# IR2101_irfz44.net
KiCad netlist of a schematic drawn in Altium Designer
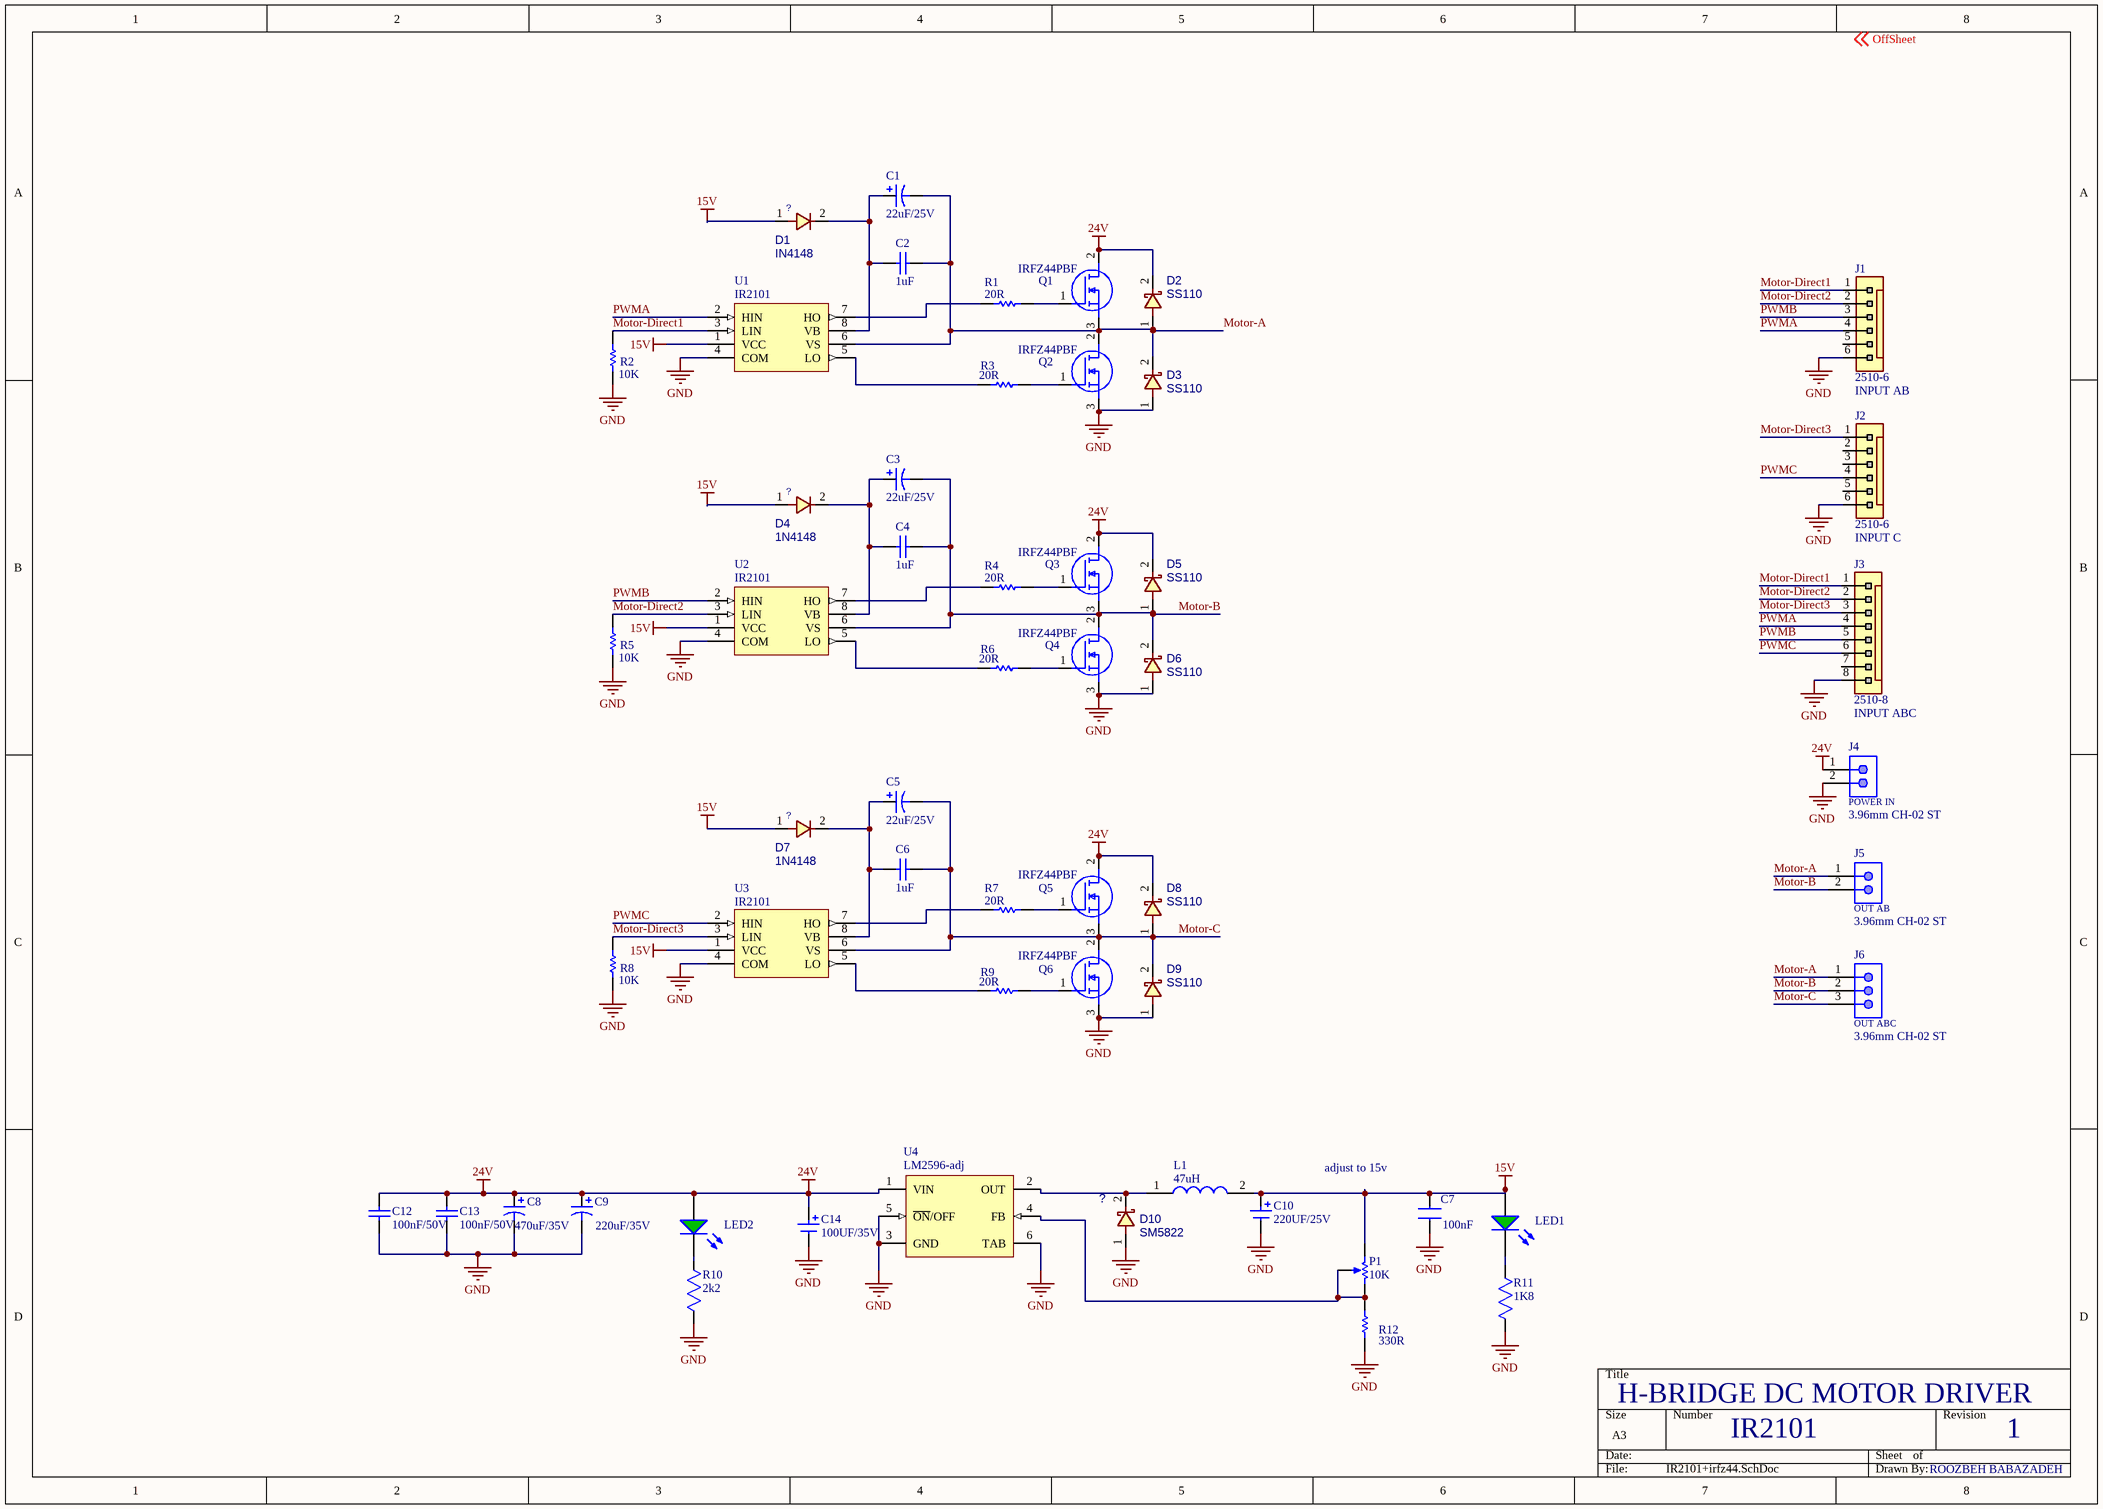
[diagram p0: IR2101+irfz44.SchDoc]

(export (version "E")
  (design (tool "Eeschema 10.0.6"))
  (components
    (comp (ref "C1")
      (value "22uF/25V")
      (footprint "C_EL_6X11")
      (description "Polarized Capacitor (Radial)")
      (fields (field (name "PUBLISHER") "Altium Limited"))
      (libsource (lib "Miscellaneous Devices") (part "Cap Pol1"))
    )
    (comp (ref "C2")
      (value "1uF")
      (footprint "C0805E")
      (description "Capacitor")
      (fields (field (name "PUBLISHER") "Altium Limited"))
      (libsource (lib "Miscellaneous Devices") (part "Cap"))
    )
    (comp (ref "C3")
      (value "22uF/25V")
      (footprint "C_EL_6X11")
      (description "Polarized Capacitor (Radial)")
      (fields (field (name "PUBLISHER") "Altium Limited"))
      (libsource (lib "Miscellaneous Devices") (part "Cap Pol1"))
    )
    (comp (ref "C4")
      (value "1uF")
      (footprint "C0805E")
      (description "Capacitor")
      (fields (field (name "PUBLISHER") "Altium Limited"))
      (libsource (lib "Miscellaneous Devices") (part "Cap"))
    )
    (comp (ref "C5")
      (value "22uF/25V")
      (footprint "C_EL_6X11")
      (description "Polarized Capacitor (Radial)")
      (fields (field (name "PUBLISHER") "Altium Limited"))
      (libsource (lib "Miscellaneous Devices") (part "Cap Pol1"))
    )
    (comp (ref "C6")
      (value "1uF")
      (footprint "C0805E")
      (description "Capacitor")
      (fields (field (name "PUBLISHER") "Altium Limited"))
      (libsource (lib "Miscellaneous Devices") (part "Cap"))
    )
    (comp (ref "C7") (value "100nF") (footprint "C0805E") (libsource (lib "OTHER") (part "C")))
    (comp (ref "C8")
      (value "470uF/35V")
      (footprint "C_EL_10X12")
      (description "63VDC")
      (libsource (lib "My_LIB") (part "Cap 220uF"))
    )
    (comp (ref "C9")
      (value "220uF/35V")
      (footprint "C_EL_10X12")
      (description "63VDC")
      (libsource (lib "My_LIB") (part "Cap 220uF"))
    )
    (comp (ref "C10")
      (value "220UF/25V")
      (footprint "C_EL_10X12")
      (libsource (lib "OTHER") (part "CAP_ELECTRO_POLIMER"))
    )
    (comp (ref "C12")
      (value "100nF/50V")
      (footprint "C_PLY_7X6")
      (libsource (lib "My_LIB") (part "Cap 100nF"))
    )
    (comp (ref "C13")
      (value "100nF/50V")
      (footprint "C_PLY_7X6")
      (description "63VDC")
      (fields (field (name "PUBLISHER") "Altium Limited"))
      (libsource (lib "Miscellaneous Devices") (part "Cap"))
    )
    (comp (ref "C14")
      (value "100UF/35V")
      (footprint "C_EL_10X12")
      (libsource (lib "OTHER") (part "CAP_ELECTRO_POLIMER"))
    )
    (comp (ref "D1")
      (value "IN4148")
      (footprint "D_SOD123W")
      (description "DIODE, GENERAL PURPOSE, 50V/1A")
      (fields
        (field (name "MANF") "MANF")
        (field (name "MANF_P#") "1N4001")
        (field (name "ALTIUM_VALUE") "?")
      )
      (libsource (lib "diode") (part "DIODE"))
    )
    (comp (ref "D2")
      (value "SS110")
      (footprint "D_SMA")
      (description "DIODE, SCHOTTKY, 40V, 1A")
      (fields (field (name "MANF") "DIODES") (field (name "MANF_P#") "1N5819HW-7-F"))
      (libsource (lib "diode") (part "SCHOTTKY"))
    )
    (comp (ref "D3")
      (value "SS110")
      (footprint "D_SMA")
      (description "DIODE, SCHOTTKY, 40V, 1A")
      (fields (field (name "MANF") "DIODES") (field (name "MANF_P#") "1N5819HW-7-F"))
      (libsource (lib "diode") (part "SCHOTTKY"))
    )
    (comp (ref "D4")
      (value "1N4148")
      (footprint "D_SOD123W")
      (description "DIODE, GENERAL PURPOSE, 50V/1A")
      (fields
        (field (name "MANF") "MANF")
        (field (name "MANF_P#") "1N4001")
        (field (name "ALTIUM_VALUE") "?")
      )
      (libsource (lib "diode") (part "DIODE"))
    )
    (comp (ref "D5")
      (value "SS110")
      (footprint "D_SMA")
      (description "DIODE, SCHOTTKY, 40V, 1A")
      (fields (field (name "MANF") "DIODES") (field (name "MANF_P#") "1N5819HW-7-F"))
      (libsource (lib "diode") (part "SCHOTTKY"))
    )
    (comp (ref "D6")
      (value "SS110")
      (footprint "D_SMA")
      (description "DIODE, SCHOTTKY, 40V, 1A")
      (fields (field (name "MANF") "DIODES") (field (name "MANF_P#") "1N5819HW-7-F"))
      (libsource (lib "diode") (part "SCHOTTKY"))
    )
    (comp (ref "D7")
      (value "1N4148")
      (footprint "D_SOD123W")
      (description "DIODE, GENERAL PURPOSE, 50V/1A")
      (fields
        (field (name "MANF") "MANF")
        (field (name "MANF_P#") "1N4001")
        (field (name "ALTIUM_VALUE") "?")
      )
      (libsource (lib "diode") (part "DIODE"))
    )
    (comp (ref "D8")
      (value "SS110")
      (footprint "D_SMA")
      (description "DIODE, SCHOTTKY, 40V, 1A")
      (fields (field (name "MANF") "DIODES") (field (name "MANF_P#") "1N5819HW-7-F"))
      (libsource (lib "diode") (part "SCHOTTKY"))
    )
    (comp (ref "D9")
      (value "SS110")
      (footprint "D_SMA")
      (description "DIODE, SCHOTTKY, 40V, 1A")
      (fields (field (name "MANF") "DIODES") (field (name "MANF_P#") "1N5819HW-7-F"))
      (libsource (lib "diode") (part "SCHOTTKY"))
    )
    (comp (ref "D10")
      (value "SM5822")
      (footprint "D_SMB")
      (description "DIODE, SCHOTTKY, 40V, 1A")
      (fields
        (field (name "MANF") "DIODES")
        (field (name "MANF_P#") "1N5819HW-7-F")
        (field (name "ALTIUM_VALUE") "?")
      )
      (libsource (lib "diode") (part "SCHOTTKY"))
    )
    (comp (ref "J1")
      (value "2510-6")
      (footprint "WF_6")
      (description "Header, WF, Pitch: 2.54mm")
      (fields (field (name "ALTIUM_VALUE") "INPUT AB"))
      (libsource (lib "xh-xhr-wf-hhdr-hh6r") (part "HDRWF_6"))
    )
    (comp (ref "J2")
      (value "2510-6")
      (footprint "WF_6")
      (description "Header, WF, Pitch: 2.54mm")
      (fields (field (name "ALTIUM_VALUE") "INPUT C"))
      (libsource (lib "xh-xhr-wf-hhdr-hh6r") (part "HDRWF_6"))
    )
    (comp (ref "J3")
      (value "2510-8")
      (footprint "WF_8")
      (description "Header, WF, Pitch: 2.54mm")
      (fields (field (name "ALTIUM_VALUE") "INPUT ABC"))
      (libsource (lib "xh-xhr-wf-hhdr-hh6r") (part "HDRWF_8"))
    )
    (comp (ref "J4")
      (value "POWER IN")
      (footprint "PWL_2")
      (description "CH-02 ST pitch 3.96mm, Single Row, Vertical, 2pin")
      (fields
        (field (name "PART NUMBER") "61300211121")
        (field (name "PACKAGING") "3.96mm CH-02 ST")
        (field (name "PUBLISHER") "Wurth Elektronik")
      )
      (libsource (lib "sip m") (part "sip 2"))
    )
    (comp (ref "J5")
      (value "OUT AB")
      (footprint "PWL_2")
      (description "CH-02 ST pitch 3.96mm, Single Row, Vertical, 2pin")
      (fields
        (field (name "PART NUMBER") "61300211121")
        (field (name "PACKAGING") "3.96mm CH-02 ST")
        (field (name "PUBLISHER") "Wurth Elektronik")
      )
      (libsource (lib "sip m") (part "sip 2"))
    )
    (comp (ref "J6")
      (value "OUT ABC")
      (footprint "PWL_3")
      (description "CH-02 STpitch 3.96mm, Single Row, Vertical, 3pin")
      (fields
        (field (name "PART NUMBER") "61300311121")
        (field (name "PACKAGING") "3.96mm CH-02 ST")
        (field (name "PUBLISHER") "Wurth Elektronik")
      )
      (libsource (lib "sip m") (part "sip 3"))
    )
    (comp (ref "L1")
      (value "47uH")
      (footprint "CDRH127LDNP560MC-12*12")
      (description "Inductor")
      (fields
        (field (name "MANUFACTURER_PART_NUMBER") "CDRH127/LDNP-560MC")
        (field (name "MOUSER PART NUMBER") "851-CDRH127LDNP560MC")
      )
      (libsource (lib "*") (part "CDRH127_LDNP-560MC"))
    )
    (comp (ref "LED1") (value "LED3mm") (footprint "LED1206RED") (libsource (lib "OTHER") (part "LED3mm")))
    (comp (ref "LED2") (value "LED3mm") (footprint "LED1206RED") (libsource (lib "OTHER") (part "LED3mm")))
    (comp (ref "P1")
      (value "10K")
      (footprint "POT_3296W")
      (description "Potentiometer")
      (libsource (lib "My_LIB") (part "Multi-Turn"))
    )
    (comp (ref "Q1")
      (value "IRFZ44PBF")
      (footprint "TO-254")
      (description "MOSFET (N-Channel)")
      (fields (field (name "MOUSER PART NUMBER") "844-IRFZ44PBF"))
      (libsource (lib "*") (part "IRFZ44PBF"))
    )
    (comp (ref "Q2")
      (value "IRFZ44PBF")
      (footprint "TO-254")
      (description "MOSFET (N-Channel)")
      (fields (field (name "MOUSER PART NUMBER") "844-IRFZ44PBF"))
      (libsource (lib "*") (part "IRFZ44PBF"))
    )
    (comp (ref "Q3")
      (value "IRFZ44PBF")
      (footprint "TO-254")
      (description "MOSFET (N-Channel)")
      (fields (field (name "MOUSER PART NUMBER") "844-IRFZ44PBF"))
      (libsource (lib "*") (part "IRFZ44PBF"))
    )
    (comp (ref "Q4")
      (value "IRFZ44PBF")
      (footprint "TO-254")
      (description "MOSFET (N-Channel)")
      (fields (field (name "MOUSER PART NUMBER") "844-IRFZ44PBF"))
      (libsource (lib "*") (part "IRFZ44PBF"))
    )
    (comp (ref "Q5")
      (value "IRFZ44PBF")
      (footprint "TO-254")
      (description "MOSFET (N-Channel)")
      (fields (field (name "MOUSER PART NUMBER") "844-IRFZ44PBF"))
      (libsource (lib "*") (part "IRFZ44PBF"))
    )
    (comp (ref "Q6")
      (value "IRFZ44PBF")
      (footprint "TO-254")
      (description "MOSFET (N-Channel)")
      (fields (field (name "MOUSER PART NUMBER") "844-IRFZ44PBF"))
      (libsource (lib "*") (part "IRFZ44PBF"))
    )
    (comp (ref "R1")
      (value "20R")
      (footprint "R0805")
      (description "Resistor")
      (fields (field (name "PUBLISHER") "Altium Limited"))
      (libsource (lib "Miscellaneous Devices") (part "Res1"))
    )
    (comp (ref "R2")
      (value "10K")
      (footprint "R0805")
      (description "Resistor")
      (fields (field (name "PUBLISHER") "Altium Limited"))
      (libsource (lib "Miscellaneous Devices") (part "Res1"))
    )
    (comp (ref "R3")
      (value "20R")
      (footprint "R0805")
      (description "Resistor")
      (fields (field (name "PUBLISHER") "Altium Limited"))
      (libsource (lib "Miscellaneous Devices") (part "Res1"))
    )
    (comp (ref "R4")
      (value "20R")
      (footprint "R0805")
      (description "Resistor")
      (fields (field (name "PUBLISHER") "Altium Limited"))
      (libsource (lib "Miscellaneous Devices") (part "Res1"))
    )
    (comp (ref "R5")
      (value "10K")
      (footprint "R0805")
      (description "Resistor")
      (fields (field (name "PUBLISHER") "Altium Limited"))
      (libsource (lib "Miscellaneous Devices") (part "Res1"))
    )
    (comp (ref "R6")
      (value "20R")
      (footprint "R0805")
      (description "Resistor")
      (fields (field (name "PUBLISHER") "Altium Limited"))
      (libsource (lib "Miscellaneous Devices") (part "Res1"))
    )
    (comp (ref "R7")
      (value "20R")
      (footprint "R0805")
      (description "Resistor")
      (fields (field (name "Comment") "Res1") (field (name "PUBLISHER") "Altium Limited"))
      (libsource (lib "Miscellaneous Devices") (part "Res1"))
    )
    (comp (ref "R8")
      (value "10K")
      (footprint "R0805")
      (description "Resistor")
      (fields (field (name "PUBLISHER") "Altium Limited"))
      (libsource (lib "Miscellaneous Devices") (part "Res1"))
    )
    (comp (ref "R9")
      (value "20R")
      (footprint "R0805")
      (description "Resistor")
      (fields (field (name "Comment") "Res1") (field (name "PUBLISHER") "Altium Limited"))
      (libsource (lib "Miscellaneous Devices") (part "Res1"))
    )
    (comp (ref "R10") (value "2k2") (footprint "R0805") (libsource (lib "OTHER") (part "R")))
    (comp (ref "R11") (value "1K8") (footprint "R0805") (libsource (lib "OTHER") (part "R")))
    (comp (ref "R12")
      (value "330R")
      (footprint "R0805")
      (description "Resistor")
      (fields (field (name "PUBLISHER") "Altium Limited"))
      (libsource (lib "Miscellaneous Devices") (part "Res1"))
    )
    (comp (ref "U1")
      (value "IR2101")
      (footprint "SO_8")
      (description "High and Low Side Driver")
      (fields (field (name "PUBLISHER") "Altium Limited"))
      (libsource (lib "IR Interface Bridge Driver") (part "IR2101"))
    )
    (comp (ref "U2")
      (value "IR2101")
      (footprint "SO_8")
      (description "High and Low Side Driver")
      (fields (field (name "PUBLISHER") "Altium Limited"))
      (libsource (lib "IR Interface Bridge Driver") (part "IR2101"))
    )
    (comp (ref "U3")
      (value "IR2101")
      (footprint "SO_8")
      (description "High and Low Side Driver")
      (fields (field (name "PUBLISHER") "Altium Limited"))
      (libsource (lib "IR Interface Bridge Driver") (part "IR2101"))
    )
    (comp (ref "U4")
      (value "LM2596-adj")
      (footprint "to-263-5 5d2pak LM2596S")
      (libsource (lib "POWER") (part "LM2596s"))
    )
  )
  (nets
    (net (code "1") (name "/Motor-A") (class "Default")
      (node (ref "C1") (pin "2") (pinfunction "2_2") (pintype "passive"))
      (node (ref "C2") (pin "2") (pinfunction "2_2") (pintype "passive"))
      (node (ref "D2") (pin "1") (pinfunction "1_1") (pintype "passive"))
      (node (ref "D3") (pin "2") (pinfunction "2_2") (pintype "passive"))
      (node (ref "J5") (pin "1") (pinfunction "1_1") (pintype "passive"))
      (node (ref "J6") (pin "1") (pinfunction "1_1") (pintype "passive"))
      (node (ref "Q1") (pin "3") (pinfunction "S_3") (pintype "passive"))
      (node (ref "Q2") (pin "2") (pinfunction "D_2") (pintype "passive"))
      (node (ref "U1") (pin "6") (pinfunction "VS_6") (pintype "power_in"))
    )
    (net (code "2") (name "/Motor-B") (class "Default")
      (node (ref "C3") (pin "2") (pinfunction "2_2") (pintype "passive"))
      (node (ref "C4") (pin "2") (pinfunction "2_2") (pintype "passive"))
      (node (ref "D5") (pin "1") (pinfunction "1_1") (pintype "passive"))
      (node (ref "D6") (pin "2") (pinfunction "2_2") (pintype "passive"))
      (node (ref "J5") (pin "2") (pinfunction "2_2") (pintype "passive"))
      (node (ref "J6") (pin "2") (pinfunction "2_2") (pintype "passive"))
      (node (ref "Q3") (pin "3") (pinfunction "S_3") (pintype "passive"))
      (node (ref "Q4") (pin "2") (pinfunction "D_2") (pintype "passive"))
      (node (ref "U2") (pin "6") (pinfunction "VS_6") (pintype "power_in"))
    )
    (net (code "3") (name "/Motor-C") (class "Default")
      (node (ref "C5") (pin "2") (pinfunction "2_2") (pintype "passive"))
      (node (ref "C6") (pin "2") (pinfunction "2_2") (pintype "passive"))
      (node (ref "D8") (pin "1") (pinfunction "1_1") (pintype "passive"))
      (node (ref "D9") (pin "2") (pinfunction "2_2") (pintype "passive"))
      (node (ref "J6") (pin "3") (pinfunction "3_3") (pintype "passive"))
      (node (ref "Q5") (pin "3") (pinfunction "S_3") (pintype "passive"))
      (node (ref "Q6") (pin "2") (pinfunction "D_2") (pintype "passive"))
      (node (ref "U3") (pin "6") (pinfunction "VS_6") (pintype "power_in"))
    )
    (net (code "4") (name "/Motor-Direct1") (class "Default")
      (node (ref "J1") (pin "1") (pinfunction "1_1") (pintype "passive"))
      (node (ref "J3") (pin "1") (pinfunction "1_1") (pintype "passive"))
      (node (ref "R2") (pin "2") (pinfunction "2_2") (pintype "passive"))
      (node (ref "U1") (pin "3") (pinfunction "LIN_3") (pintype "input"))
    )
    (net (code "5") (name "/Motor-Direct2") (class "Default")
      (node (ref "J1") (pin "2") (pinfunction "2_2") (pintype "passive"))
      (node (ref "J3") (pin "2") (pinfunction "2_2") (pintype "passive"))
      (node (ref "R5") (pin "2") (pinfunction "2_2") (pintype "passive"))
      (node (ref "U2") (pin "3") (pinfunction "LIN_3") (pintype "input"))
    )
    (net (code "6") (name "/Motor-Direct3") (class "Default")
      (node (ref "J2") (pin "1") (pinfunction "1_1") (pintype "passive"))
      (node (ref "J3") (pin "3") (pinfunction "3_3") (pintype "passive"))
      (node (ref "R8") (pin "2") (pinfunction "2_2") (pintype "passive"))
      (node (ref "U3") (pin "3") (pinfunction "LIN_3") (pintype "input"))
    )
    (net (code "7") (name "/PWMA") (class "Default")
      (node (ref "J1") (pin "4") (pinfunction "4_4") (pintype "passive"))
      (node (ref "J3") (pin "4") (pinfunction "4_4") (pintype "passive"))
      (node (ref "U1") (pin "2") (pinfunction "HIN_2") (pintype "input"))
    )
    (net (code "8") (name "/PWMB") (class "Default")
      (node (ref "J1") (pin "3") (pinfunction "3_3") (pintype "passive"))
      (node (ref "J3") (pin "5") (pinfunction "5_5") (pintype "passive"))
      (node (ref "U2") (pin "2") (pinfunction "HIN_2") (pintype "input"))
    )
    (net (code "9") (name "/PWMC") (class "Default")
      (node (ref "J2") (pin "4") (pinfunction "4_4") (pintype "passive"))
      (node (ref "J3") (pin "6") (pinfunction "6_6") (pintype "passive"))
      (node (ref "U3") (pin "2") (pinfunction "HIN_2") (pintype "input"))
    )
    (net (code "10") (name "15V") (class "Default")
      (node (ref "C10") (pin "1") (pinfunction "1_1") (pintype "passive"))
      (node (ref "C7") (pin "2") (pintype "passive"))
      (node (ref "D1") (pin "1") (pinfunction "1_1") (pintype "passive"))
      (node (ref "D4") (pin "1") (pinfunction "1_1") (pintype "passive"))
      (node (ref "D7") (pin "1") (pinfunction "1_1") (pintype "passive"))
      (node (ref "L1") (pin "2") (pinfunction "2_2") (pintype "passive"))
      (node (ref "LED1") (pin "1") (pinfunction "A_1") (pintype "passive"))
      (node (ref "P1") (pin "3") (pinfunction "BOT_3") (pintype "passive"))
      (node (ref "U1") (pin "1") (pinfunction "VCC_1") (pintype "power_in"))
      (node (ref "U2") (pin "1") (pinfunction "VCC_1") (pintype "power_in"))
      (node (ref "U3") (pin "1") (pinfunction "VCC_1") (pintype "power_in"))
    )
    (net (code "11") (name "24V") (class "Default")
      (node (ref "C12") (pin "2") (pinfunction "2_2") (pintype "passive"))
      (node (ref "C13") (pin "2") (pinfunction "2_2") (pintype "passive"))
      (node (ref "C14") (pin "1") (pinfunction "1_1") (pintype "passive"))
      (node (ref "C8") (pin "1") (pinfunction "1_1") (pintype "passive"))
      (node (ref "C9") (pin "1") (pinfunction "1_1") (pintype "passive"))
      (node (ref "D2") (pin "2") (pinfunction "2_2") (pintype "passive"))
      (node (ref "D5") (pin "2") (pinfunction "2_2") (pintype "passive"))
      (node (ref "D8") (pin "2") (pinfunction "2_2") (pintype "passive"))
      (node (ref "J4") (pin "1") (pinfunction "1_1") (pintype "passive"))
      (node (ref "LED2") (pin "1") (pinfunction "A_1") (pintype "passive"))
      (node (ref "Q1") (pin "2") (pinfunction "D_2") (pintype "passive"))
      (node (ref "Q3") (pin "2") (pinfunction "D_2") (pintype "passive"))
      (node (ref "Q5") (pin "2") (pinfunction "D_2") (pintype "passive"))
      (node (ref "U4") (pin "1") (pinfunction "VIN_1") (pintype "power_in"))
    )
    (net (code "12") (name "GND") (class "Default")
      (node (ref "C10") (pin "2") (pinfunction "2_2") (pintype "passive"))
      (node (ref "C12") (pin "1") (pinfunction "1_1") (pintype "passive"))
      (node (ref "C13") (pin "1") (pinfunction "1_1") (pintype "passive"))
      (node (ref "C14") (pin "2") (pinfunction "2_2") (pintype "passive"))
      (node (ref "C7") (pin "1") (pintype "passive"))
      (node (ref "C8") (pin "2") (pinfunction "2_2") (pintype "passive"))
      (node (ref "C9") (pin "2") (pinfunction "2_2") (pintype "passive"))
      (node (ref "D10") (pin "1") (pinfunction "1_1") (pintype "passive"))
      (node (ref "D3") (pin "1") (pinfunction "1_1") (pintype "passive"))
      (node (ref "D6") (pin "1") (pinfunction "1_1") (pintype "passive"))
      (node (ref "D9") (pin "1") (pinfunction "1_1") (pintype "passive"))
      (node (ref "J1") (pin "6") (pinfunction "6_6") (pintype "passive"))
      (node (ref "J2") (pin "6") (pinfunction "6_6") (pintype "passive"))
      (node (ref "J3") (pin "8") (pinfunction "8_8") (pintype "passive"))
      (node (ref "J4") (pin "2") (pinfunction "2_2") (pintype "passive"))
      (node (ref "Q2") (pin "3") (pinfunction "S_3") (pintype "passive"))
      (node (ref "Q4") (pin "3") (pinfunction "S_3") (pintype "passive"))
      (node (ref "Q6") (pin "3") (pinfunction "S_3") (pintype "passive"))
      (node (ref "R10") (pin "2") (pintype "passive"))
      (node (ref "R11") (pin "2") (pintype "passive"))
      (node (ref "R12") (pin "1") (pinfunction "1_1") (pintype "passive"))
      (node (ref "R2") (pin "1") (pinfunction "1_1") (pintype "passive"))
      (node (ref "R5") (pin "1") (pinfunction "1_1") (pintype "passive"))
      (node (ref "R8") (pin "1") (pinfunction "1_1") (pintype "passive"))
      (node (ref "U1") (pin "4") (pinfunction "COM_4") (pintype "power_in"))
      (node (ref "U2") (pin "4") (pinfunction "COM_4") (pintype "power_in"))
      (node (ref "U3") (pin "4") (pinfunction "COM_4") (pintype "power_in"))
      (node (ref "U4") (pin "3") (pinfunction "GND_3") (pintype "power_in"))
      (node (ref "U4") (pin "5") (pinfunction "~{ON}/OFF_5") (pintype "input"))
      (node (ref "U4") (pin "6") (pinfunction "TAB_6") (pintype "power_in"))
    )
    (net (code "13") (name "Net-(LED1-K)") (class "Default")
      (node (ref "LED1") (pin "2") (pinfunction "K_2") (pintype "passive"))
      (node (ref "R11") (pin "1") (pintype "passive"))
    )
    (net (code "14") (name "Net-(LED2-K)") (class "Default")
      (node (ref "LED2") (pin "2") (pinfunction "K_2") (pintype "passive"))
      (node (ref "R10") (pin "1") (pintype "passive"))
    )
    (net (code "15") (name "Net-(P1-TAP)") (class "Default")
      (node (ref "P1") (pin "1") (pinfunction "TOP_1") (pintype "passive"))
      (node (ref "P1") (pin "2") (pinfunction "TAP_2") (pintype "passive"))
      (node (ref "R12") (pin "2") (pinfunction "2_2") (pintype "passive"))
      (node (ref "U4") (pin "4") (pinfunction "FB_4") (pintype "input"))
    )
    (net (code "16") (name "Net-(Q1-G)") (class "Default")
      (node (ref "Q1") (pin "1") (pinfunction "G_1") (pintype "passive"))
      (node (ref "R1") (pin "2") (pinfunction "2_2") (pintype "passive"))
    )
    (net (code "17") (name "Net-(Q2-G)") (class "Default")
      (node (ref "Q2") (pin "1") (pinfunction "G_1") (pintype "passive"))
      (node (ref "R3") (pin "2") (pinfunction "2_2") (pintype "passive"))
    )
    (net (code "18") (name "Net-(Q3-G)") (class "Default")
      (node (ref "Q3") (pin "1") (pinfunction "G_1") (pintype "passive"))
      (node (ref "R4") (pin "2") (pinfunction "2_2") (pintype "passive"))
    )
    (net (code "19") (name "Net-(Q4-G)") (class "Default")
      (node (ref "Q4") (pin "1") (pinfunction "G_1") (pintype "passive"))
      (node (ref "R6") (pin "2") (pinfunction "2_2") (pintype "passive"))
    )
    (net (code "20") (name "Net-(Q5-G)") (class "Default")
      (node (ref "Q5") (pin "1") (pinfunction "G_1") (pintype "passive"))
      (node (ref "R7") (pin "2") (pinfunction "2_2") (pintype "passive"))
    )
    (net (code "21") (name "Net-(Q6-G)") (class "Default")
      (node (ref "Q6") (pin "1") (pinfunction "G_1") (pintype "passive"))
      (node (ref "R9") (pin "2") (pinfunction "2_2") (pintype "passive"))
    )
    (net (code "22") (name "Net-(U1-HO)") (class "Default")
      (node (ref "R1") (pin "1") (pinfunction "1_1") (pintype "passive"))
      (node (ref "U1") (pin "7") (pinfunction "HO_7") (pintype "output"))
    )
    (net (code "23") (name "Net-(U1-LO)") (class "Default")
      (node (ref "R3") (pin "1") (pinfunction "1_1") (pintype "passive"))
      (node (ref "U1") (pin "5") (pinfunction "LO_5") (pintype "output"))
    )
    (net (code "24") (name "Net-(U1-VB)") (class "Default")
      (node (ref "C1") (pin "1") (pinfunction "1_1") (pintype "passive"))
      (node (ref "C2") (pin "1") (pinfunction "1_1") (pintype "passive"))
      (node (ref "D1") (pin "2") (pinfunction "2_2") (pintype "passive"))
      (node (ref "U1") (pin "8") (pinfunction "VB_8") (pintype "power_in"))
    )
    (net (code "25") (name "Net-(U2-HO)") (class "Default")
      (node (ref "R4") (pin "1") (pinfunction "1_1") (pintype "passive"))
      (node (ref "U2") (pin "7") (pinfunction "HO_7") (pintype "output"))
    )
    (net (code "26") (name "Net-(U2-LO)") (class "Default")
      (node (ref "R6") (pin "1") (pinfunction "1_1") (pintype "passive"))
      (node (ref "U2") (pin "5") (pinfunction "LO_5") (pintype "output"))
    )
    (net (code "27") (name "Net-(U2-VB)") (class "Default")
      (node (ref "C3") (pin "1") (pinfunction "1_1") (pintype "passive"))
      (node (ref "C4") (pin "1") (pinfunction "1_1") (pintype "passive"))
      (node (ref "D4") (pin "2") (pinfunction "2_2") (pintype "passive"))
      (node (ref "U2") (pin "8") (pinfunction "VB_8") (pintype "power_in"))
    )
    (net (code "28") (name "Net-(U3-HO)") (class "Default")
      (node (ref "R7") (pin "1") (pinfunction "1_1") (pintype "passive"))
      (node (ref "U3") (pin "7") (pinfunction "HO_7") (pintype "output"))
    )
    (net (code "29") (name "Net-(U3-LO)") (class "Default")
      (node (ref "R9") (pin "1") (pinfunction "1_1") (pintype "passive"))
      (node (ref "U3") (pin "5") (pinfunction "LO_5") (pintype "output"))
    )
    (net (code "30") (name "Net-(U3-VB)") (class "Default")
      (node (ref "C5") (pin "1") (pinfunction "1_1") (pintype "passive"))
      (node (ref "C6") (pin "1") (pinfunction "1_1") (pintype "passive"))
      (node (ref "D7") (pin "2") (pinfunction "2_2") (pintype "passive"))
      (node (ref "U3") (pin "8") (pinfunction "VB_8") (pintype "power_in"))
    )
    (net (code "31") (name "Net-(U4-OUT)") (class "Default")
      (node (ref "D10") (pin "2") (pinfunction "2_2") (pintype "passive"))
      (node (ref "L1") (pin "1") (pinfunction "1_1") (pintype "passive"))
      (node (ref "U4") (pin "2") (pinfunction "OUT_2") (pintype "power_in"))
    )
    (net (code "33") (name "unconnected-(J1-Pad5)") (class "Default")
      (node (ref "J1") (pin "5") (pinfunction "5_5") (pintype "passive"))
    )
    (net (code "34") (name "unconnected-(J2-Pad2)") (class "Default")
      (node (ref "J2") (pin "2") (pinfunction "2_2") (pintype "passive"))
    )
    (net (code "35") (name "unconnected-(J2-Pad3)") (class "Default")
      (node (ref "J2") (pin "3") (pinfunction "3_3") (pintype "passive"))
    )
    (net (code "36") (name "unconnected-(J2-Pad5)") (class "Default")
      (node (ref "J2") (pin "5") (pinfunction "5_5") (pintype "passive"))
    )
    (net (code "37") (name "unconnected-(J3-Pad7)") (class "Default")
      (node (ref "J3") (pin "7") (pinfunction "7_7") (pintype "passive"))
    )
  )
)
